# Power.net
KiCad netlist of a schematic drawn in Altium Designer
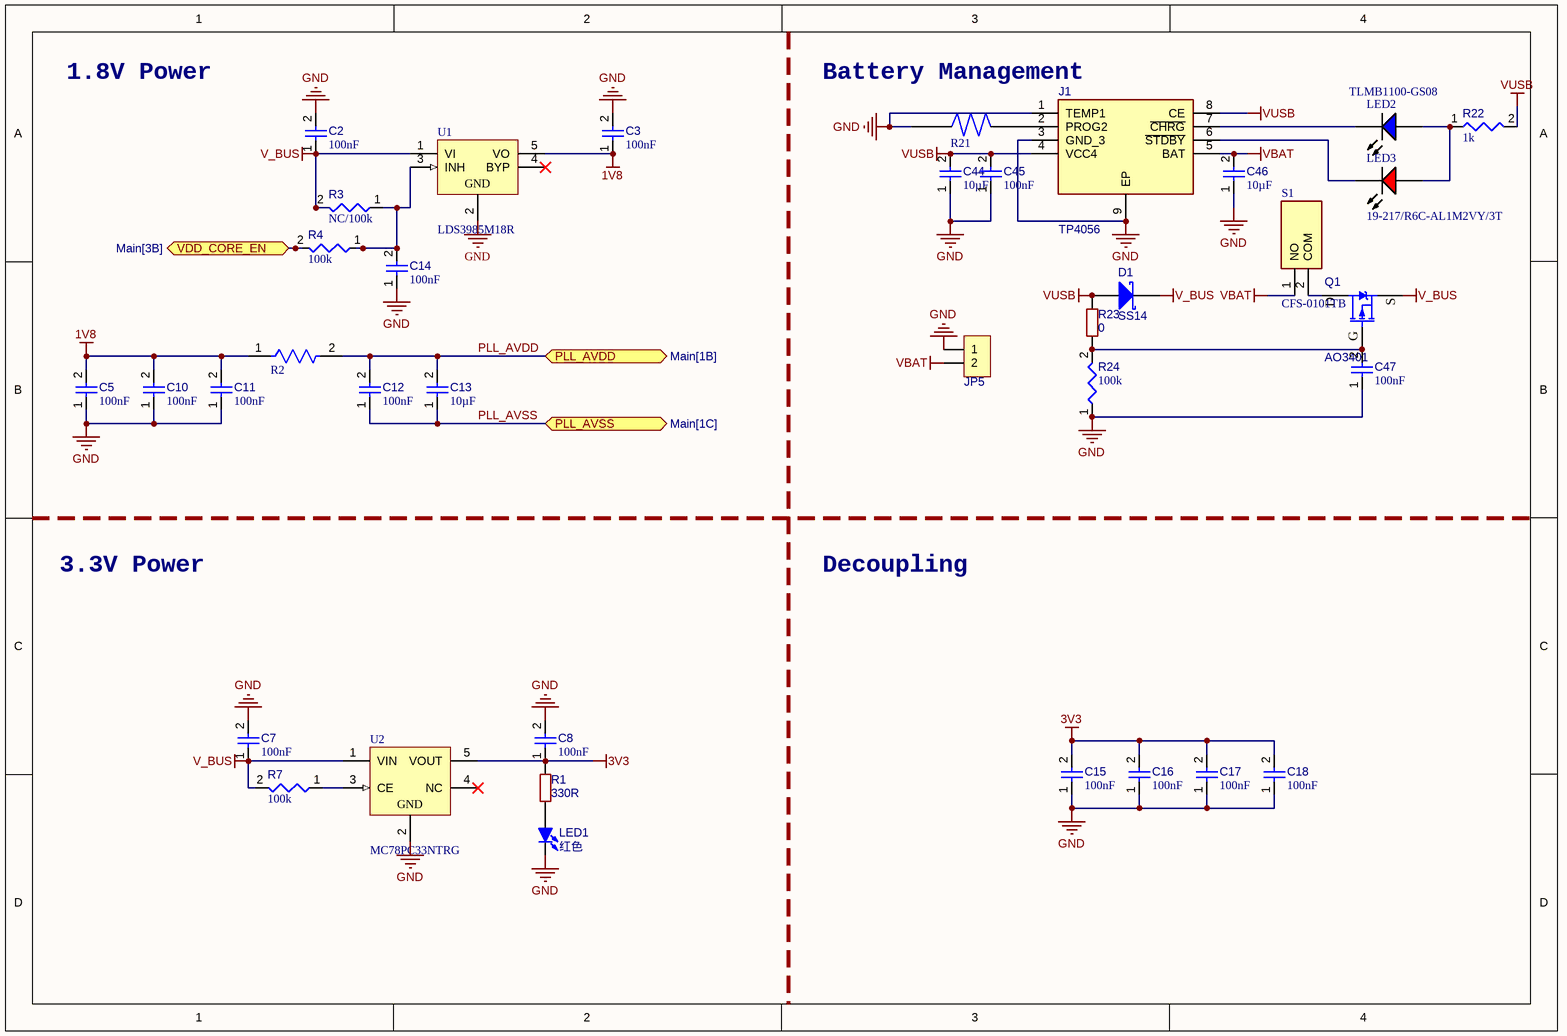
[diagram p0: Power.SchDoc]

(export (version "E")
  (design (tool "Eeschema 10.0.6"))
  (components
    (comp (ref "C2")
      (value "100nF")
      (footprint "CAPC1608X90X40NL10T20")
      (description "Chip Capacitor, 100 nF, +/- 10%, 50 V, 0603 (1608 Metric)")
      (fields (field (name "TOLERANCE") "10%") (field (name "Comment") "Capacitor 100 nF +/-10% 50 V 0603"))
      (libsource (lib "Rice University") (part "CAP-NP-2"))
    )
    (comp (ref "C3")
      (value "100nF")
      (footprint "CAPC1608X90X40NL10T20")
      (description "Chip Capacitor, 100 nF, +/- 10%, 50 V, 0603 (1608 Metric)")
      (fields (field (name "TOLERANCE") "10%") (field (name "Comment") "Capacitor 100 nF +/-10% 50 V 0603"))
      (libsource (lib "Rice University") (part "CAP-NP-2"))
    )
    (comp (ref "C5")
      (value "100nF")
      (footprint "CAPC1608X90X40NL10T20")
      (description "Chip Capacitor, 100 nF, +/- 10%, 50 V, 0603 (1608 Metric)")
      (fields (field (name "TOLERANCE") "10%") (field (name "Comment") "Capacitor 100 nF +/-10% 50 V 0603"))
      (libsource (lib "Rice University") (part "CAP-NP-2"))
    )
    (comp (ref "C7")
      (value "100nF")
      (footprint "CAPC1608X90X40NL10T20")
      (description "Chip Capacitor, 100 nF, +/- 10%, 50 V, 0603 (1608 Metric)")
      (fields (field (name "TOLERANCE") "10%") (field (name "Comment") "Capacitor 100 nF +/-10% 50 V 0603"))
      (libsource (lib "Rice University") (part "CAP-NP-2"))
    )
    (comp (ref "C8")
      (value "100nF")
      (footprint "CAPC1608X90X40NL10T20")
      (description "Chip Capacitor, 100 nF, +/- 10%, 50 V, 0603 (1608 Metric)")
      (fields (field (name "TOLERANCE") "10%") (field (name "Comment") "Capacitor 100 nF +/-10% 50 V 0603"))
      (libsource (lib "Rice University") (part "CAP-NP-2"))
    )
    (comp (ref "C10")
      (value "100nF")
      (footprint "CAPC1608X90X40NL10T20")
      (description "Chip Capacitor, 100 nF, +/- 10%, 50 V, 0603 (1608 Metric)")
      (fields (field (name "TOLERANCE") "10%") (field (name "Comment") "Capacitor 100 nF +/-10% 50 V 0603"))
      (libsource (lib "Rice University") (part "CAP-NP-2"))
    )
    (comp (ref "C11")
      (value "100nF")
      (footprint "CAPC1608X90X40NL10T20")
      (description "Chip Capacitor, 100 nF, +/- 10%, 50 V, 0603 (1608 Metric)")
      (fields (field (name "TOLERANCE") "10%") (field (name "Comment") "Capacitor 100 nF +/-10% 50 V 0603"))
      (libsource (lib "Rice University") (part "CAP-NP-2"))
    )
    (comp (ref "C12")
      (value "100nF")
      (footprint "CAPC1608X90X40NL10T20")
      (description "Chip Capacitor, 100 nF, +/- 10%, 50 V, 0603 (1608 Metric)")
      (fields (field (name "TOLERANCE") "10%") (field (name "Comment") "Capacitor 100 nF +/-10% 50 V 0603"))
      (libsource (lib "Rice University") (part "CAP-NP-2"))
    )
    (comp (ref "C13")
      (value "10µF")
      (footprint "CAPC0603(1608)100_L")
      (description "Chip Capacitor, 10µF +/-20%, 10V, 0603, Thickness 1 mm")
      (fields (field (name "TOLERANCE") "10%") (field (name "Comment") "Capacitor 10µF +/-20% 10V 0603"))
      (libsource (lib "Rice University") (part "CAP-NP-2"))
    )
    (comp (ref "C14")
      (value "100nF")
      (footprint "CAPC1608X90X40NL10T20")
      (description "Chip Capacitor, 100 nF, +/- 10%, 50 V, 0603 (1608 Metric)")
      (fields (field (name "TOLERANCE") "10%") (field (name "Comment") "Capacitor 100 nF +/-10% 50 V 0603"))
      (libsource (lib "Rice University") (part "CAP-NP-2"))
    )
    (comp (ref "C15")
      (value "100nF")
      (footprint "CAPC1608X90X40NL10T20")
      (description "Chip Capacitor, 100 nF, +/- 10%, 50 V, 0603 (1608 Metric)")
      (fields (field (name "TOLERANCE") "10%") (field (name "Comment") "Capacitor 100 nF +/-10% 50 V 0603"))
      (libsource (lib "Rice University") (part "CAP-NP-2"))
    )
    (comp (ref "C16")
      (value "100nF")
      (footprint "CAPC1608X90X40NL10T20")
      (description "Chip Capacitor, 100 nF, +/- 10%, 50 V, 0603 (1608 Metric)")
      (fields (field (name "TOLERANCE") "10%") (field (name "Comment") "Capacitor 100 nF +/-10% 50 V 0603"))
      (libsource (lib "Rice University") (part "CAP-NP-2"))
    )
    (comp (ref "C17")
      (value "100nF")
      (footprint "CAPC1608X90X40NL10T20")
      (description "Chip Capacitor, 100 nF, +/- 10%, 50 V, 0603 (1608 Metric)")
      (fields (field (name "TOLERANCE") "10%") (field (name "Comment") "Capacitor 100 nF +/-10% 50 V 0603"))
      (libsource (lib "Rice University") (part "CAP-NP-2"))
    )
    (comp (ref "C18")
      (value "100nF")
      (footprint "CAPC1608X90X40NL10T20")
      (description "Chip Capacitor, 100 nF, +/- 10%, 50 V, 0603 (1608 Metric)")
      (fields (field (name "TOLERANCE") "10%") (field (name "Comment") "Capacitor 100 nF +/-10% 50 V 0603"))
      (libsource (lib "Rice University") (part "CAP-NP-2"))
    )
    (comp (ref "C44")
      (value "10µF")
      (footprint "CAPC0603(1608)100_L")
      (description "Chip Capacitor, 10µF +/-20%, 10V, 0603, Thickness 1 mm")
      (fields (field (name "TOLERANCE") "10%") (field (name "Comment") "Capacitor 10µF +/-20% 10V 0603"))
      (libsource (lib "Rice University") (part "CAP-NP-2"))
    )
    (comp (ref "C45")
      (value "100nF")
      (footprint "CAPC1608X90X40NL10T20")
      (description "Chip Capacitor, 100 nF, +/- 10%, 50 V, 0603 (1608 Metric)")
      (fields (field (name "TOLERANCE") "10%") (field (name "Comment") "Capacitor 100 nF +/-10% 50 V 0603"))
      (libsource (lib "Rice University") (part "CAP-NP-2"))
    )
    (comp (ref "C46")
      (value "10µF")
      (footprint "CAPC0603(1608)100_L")
      (description "Chip Capacitor, 10µF +/-20%, 10V, 0603, Thickness 1 mm")
      (fields (field (name "TOLERANCE") "10%") (field (name "Comment") "Capacitor 10µF +/-20% 10V 0603"))
      (libsource (lib "Rice University") (part "CAP-NP-2"))
    )
    (comp (ref "C47")
      (value "100nF")
      (footprint "CAPC1608X90X40NL10T20")
      (description "Chip Capacitor, 100 nF, +/- 10%, 50 V, 0603 (1608 Metric)")
      (fields (field (name "TOLERANCE") "10%") (field (name "Comment") "Capacitor 100 nF +/-10% 50 V 0603"))
      (libsource (lib "Rice University") (part "CAP-NP-2"))
    )
    (comp (ref "D1")
      (value "SS14")
      (footprint "SMA")
      (description "肖特基二极管")
      (libsource (lib "0.2 - 二极管-TVS-ESD-整流桥-放电管") (part "SS14"))
    )
    (comp (ref "J1")
      (value "TP4056")
      (footprint "SamacSys:SOIC127P600X175-9N")
      (description "Connector")
      (libsource (lib "*") (part "TP4056"))
    )
    (comp (ref "JP5")
      (value "HDR-1X2")
      (footprint "XH2.54-LS-2P")
      (description "2P接插件")
      (libsource (lib "5.5 - 2.54mm连接器(KF2EDGK_XH2.54_2.54排针排母)") (part "Header 2"))
    )
    (comp (ref "LED1")
      (value "红色")
      (footprint "LED0603_R")
      (description "贴片LED")
      (libsource (lib "0.3 - LED发光二极管-IR二极管_接收管-光耦") (part "LED-SMD"))
    )
    (comp (ref "LED2")
      (value "TLMB1100-GS08")
      (footprint "VISH-TLMX1100-2_V")
      (description "Blue LED, 10 mA, 3.9 V, -40 to 100 degC, 2-Pin SMD (0603), RoHS, Tape and Reel")
      (fields (field (name "POWER") "68mW") (field (name "MANUFACTURER") "Vishay Semiconductor"))
      (libsource (lib "Rice University") (part "LED-BLUE-AK-2"))
    )
    (comp (ref "LED3")
      (value "19-217/R6C-AL1M2VY/3T")
      (footprint "EVRL-0603-2_V")
      (description "Chip LED, Red, 5 V, 25 mA, -40 to 85 degC, 2-Pin SMD (0603), RoHS, Tape and Reel")
      (fields (field (name "MANUFACTURER") "Everlight Electronics"))
      (libsource (lib "Rice University") (part "LED-RED-AK-2"))
    )
    (comp (ref "Q1")
      (value "AO3401")
      (footprint "SOT23-3N")
      (description "P沟道 30V/4.2A")
      (libsource (lib "0.4 - 三极管-场效应管-可控硅") (part "AO3401"))
    )
    (comp (ref "R1")
      (value "330R")
      (footprint "R0603_NS")
      (description "贴片电阻")
      (libsource (lib "") (part "R_1"))
    )
    (comp (ref "R2")
      (value "CRGP0603F100R")
      (footprint "FP-CRGP0603-IPC_B")
      (description "Res Thick Film 0603 100 Ohm 1% 0.25W(1/4W) ±100ppm/C Pad SMD T/R")
      (libsource (lib "Rice University") (part "1029c3af85768c4190bb7ad29bc67b5"))
    )
    (comp (ref "R3")
      (value "NC/100k")
      (footprint "RESC1608X55X25ML10T15")
      (description "Chip Resistor, 100 KOhm, +/- 1%, 0.1 W, -55 to 155 degC, 0603 (1608 Metric)")
      (fields (field (name "TOLERANCE") "1%") (field (name "POWER") "100mW"))
      (libsource (lib "Rice University") (part "RES-2"))
    )
    (comp (ref "R4")
      (value "100k")
      (footprint "RESC1608X55X25ML10T15")
      (description "Chip Resistor, 100 KOhm, +/- 1%, 0.1 W, -55 to 155 degC, 0603 (1608 Metric)")
      (fields (field (name "TOLERANCE") "1%") (field (name "POWER") "100mW"))
      (libsource (lib "Rice University") (part "RES-2"))
    )
    (comp (ref "R7")
      (value "100k")
      (footprint "RESC1608X55X25ML10T15")
      (description "Chip Resistor, 100 KOhm, +/- 1%, 0.1 W, -55 to 155 degC, 0603 (1608 Metric)")
      (fields (field (name "TOLERANCE") "1%") (field (name "POWER") "100mW"))
      (libsource (lib "Rice University") (part "RES-2"))
    )
    (comp (ref "R21")
      (value "CRCW06031K20FKTA")
      (footprint "CRCW06031K20FKTA-Footprint-1")
      (description "Res Thick Film 0603 1.2K Ohm 1% 1/10W ±100ppm/°C Molded SMD SMD Paper T/R")
      (libsource (lib "Rice University") (part "CRCW06031K20FKTA-Symbol-1"))
    )
    (comp (ref "R22")
      (value "1k")
      (footprint "RESC1608X55X25ML10T15")
      (description "Chip Resistor, 1 KOhm, +/-1%, 0.1 W, -55 to 155 degC, 0603 (1608 Metric)")
      (fields (field (name "POWER") "100mW") (field (name "TOLERANCE") "1%"))
      (libsource (lib "Rice University") (part "RES-2"))
    )
    (comp (ref "R23")
      (value "0")
      (footprint "R0603_NS")
      (description "贴片电阻")
      (libsource (lib "0.1 - 电阻-电容-电感-晶振-晶体-磁珠-电位器-法拉电容-馈通电容") (part "R"))
    )
    (comp (ref "R24")
      (value "100k")
      (footprint "RESC1608X55X25ML10T15")
      (description "Chip Resistor, 100 KOhm, +/- 1%, 0.1 W, -55 to 155 degC, 0603 (1608 Metric)")
      (fields (field (name "TOLERANCE") "1%") (field (name "POWER") "100mW"))
      (libsource (lib "Rice University") (part "RES-2"))
    )
    (comp (ref "S1")
      (value "CFS-0101TB")
      (footprint "SamacSys:CFS0101TB")
      (description "Switch")
      (fields (field (name "MOUSER PART NUMBER") "229-CFS-0101TB"))
      (libsource (lib "*") (part "CFS-0101TB"))
    )
    (comp (ref "U1")
      (value "LDS3985M18R")
      (footprint "SOT23-5L_N")
      (description "LDS3985 Series 1.8 V 300 mA Fixed Surface Mount Voltage Regulator - SOT-23-5")
      (libsource (lib "Rice University") (part "PM-REG-LD3985-SOT5"))
    )
    (comp (ref "U2")
      (value "MC78PC33NTRG")
      (footprint "ONSC-SOT-23-5-1212-01_O_V")
      (fields (field (name "MANUFACTURER") "ON Semiconductor") (field (name "POWER") "250mW"))
      (libsource (lib "Rice University") (part "ONSC-MC78PC-SOT-23-5"))
    )
  )
  (nets
    (net (code "1") (name "/PLL_AVDD") (class "Default")
      (node (ref "C12") (pin "2") (pinfunction "2_2") (pintype "passive"))
      (node (ref "C13") (pin "2") (pinfunction "2_2") (pintype "passive"))
      (node (ref "R2") (pin "2") (pinfunction "2_2") (pintype "passive"))
    )
    (net (code "2") (name "/PLL_AVSS") (class "Default")
      (node (ref "C12") (pin "1") (pinfunction "1_1") (pintype "passive"))
      (node (ref "C13") (pin "1") (pinfunction "1_1") (pintype "passive"))
    )
    (net (code "3") (name "/VDD_CORE_EN") (class "Default")
      (node (ref "R4") (pin "2") (pinfunction "2_2") (pintype "passive"))
    )
    (net (code "4") (name "1V8") (class "Default")
      (node (ref "C10") (pin "2") (pinfunction "2_2") (pintype "passive"))
      (node (ref "C11") (pin "2") (pinfunction "2_2") (pintype "passive"))
      (node (ref "C3") (pin "1") (pinfunction "1_1") (pintype "passive"))
      (node (ref "C5") (pin "2") (pinfunction "2_2") (pintype "passive"))
      (node (ref "R2") (pin "1") (pinfunction "1_1") (pintype "passive"))
      (node (ref "U1") (pin "5") (pinfunction "VO_5") (pintype "power_in"))
    )
    (net (code "5") (name "3V3") (class "Default")
      (node (ref "C15") (pin "2") (pinfunction "2_2") (pintype "passive"))
      (node (ref "C16") (pin "2") (pinfunction "2_2") (pintype "passive"))
      (node (ref "C17") (pin "2") (pinfunction "2_2") (pintype "passive"))
      (node (ref "C18") (pin "2") (pinfunction "2_2") (pintype "passive"))
      (node (ref "C8") (pin "1") (pinfunction "1_1") (pintype "passive"))
      (node (ref "R1") (pin "1") (pinfunction "1_1") (pintype "passive"))
      (node (ref "U2") (pin "5") (pinfunction "VOUT_5") (pintype "power_in"))
    )
    (net (code "6") (name "GND") (class "Default")
      (node (ref "C10") (pin "1") (pinfunction "1_1") (pintype "passive"))
      (node (ref "C11") (pin "1") (pinfunction "1_1") (pintype "passive"))
      (node (ref "C14") (pin "1") (pinfunction "1_1") (pintype "passive"))
      (node (ref "C15") (pin "1") (pinfunction "1_1") (pintype "passive"))
      (node (ref "C16") (pin "1") (pinfunction "1_1") (pintype "passive"))
      (node (ref "C17") (pin "1") (pinfunction "1_1") (pintype "passive"))
      (node (ref "C18") (pin "1") (pinfunction "1_1") (pintype "passive"))
      (node (ref "C2") (pin "2") (pinfunction "2_2") (pintype "passive"))
      (node (ref "C3") (pin "2") (pinfunction "2_2") (pintype "passive"))
      (node (ref "C44") (pin "1") (pinfunction "1_1") (pintype "passive"))
      (node (ref "C45") (pin "1") (pinfunction "1_1") (pintype "passive"))
      (node (ref "C46") (pin "1") (pinfunction "1_1") (pintype "passive"))
      (node (ref "C47") (pin "1") (pinfunction "1_1") (pintype "passive"))
      (node (ref "C5") (pin "1") (pinfunction "1_1") (pintype "passive"))
      (node (ref "C7") (pin "2") (pinfunction "2_2") (pintype "passive"))
      (node (ref "C8") (pin "2") (pinfunction "2_2") (pintype "passive"))
      (node (ref "J1") (pin "1") (pinfunction "TEMP1_1") (pintype "passive"))
      (node (ref "J1") (pin "3") (pinfunction "GND_3_3") (pintype "passive"))
      (node (ref "J1") (pin "9") (pinfunction "EP_9") (pintype "passive"))
      (node (ref "JP5") (pin "1") (pinfunction "1_1") (pintype "passive"))
      (node (ref "LED1") (pin "2") (pinfunction "K_2") (pintype "passive"))
      (node (ref "R21") (pin "1") (pinfunction "1_1") (pintype "passive"))
      (node (ref "R24") (pin "1") (pinfunction "1_1") (pintype "passive"))
      (node (ref "U1") (pin "2") (pinfunction "GND_2") (pintype "power_in"))
      (node (ref "U2") (pin "2") (pinfunction "GND_2") (pintype "power_in"))
    )
    (net (code "7") (name "Net-(J1-PROG2)") (class "Default")
      (node (ref "J1") (pin "2") (pinfunction "PROG2_2") (pintype "passive"))
      (node (ref "R21") (pin "2") (pinfunction "2_2") (pintype "passive"))
    )
    (net (code "8") (name "Net-(J1-~{CHRG})") (class "Default")
      (node (ref "J1") (pin "7") (pinfunction "~{CHRG}_7") (pintype "passive"))
      (node (ref "LED2") (pin "2") (pinfunction "K_2") (pintype "passive"))
    )
    (net (code "9") (name "Net-(J1-~{STDBY})") (class "Default")
      (node (ref "J1") (pin "6") (pinfunction "~{STDBY}_6") (pintype "passive"))
      (node (ref "LED3") (pin "2") (pinfunction "K_2") (pintype "passive"))
    )
    (net (code "10") (name "Net-(LED1-A)") (class "Default")
      (node (ref "LED1") (pin "1") (pinfunction "A_1") (pintype "passive"))
      (node (ref "R1") (pin "2") (pinfunction "2_2") (pintype "passive"))
    )
    (net (code "11") (name "Net-(LED2-A)") (class "Default")
      (node (ref "LED2") (pin "1") (pinfunction "A_1") (pintype "passive"))
      (node (ref "LED3") (pin "1") (pinfunction "A_1") (pintype "passive"))
      (node (ref "R22") (pin "1") (pinfunction "1_1") (pintype "passive"))
    )
    (net (code "12") (name "Net-(Q1-D)") (class "Default")
      (node (ref "Q1") (pin "3") (pinfunction "D_3") (pintype "passive"))
      (node (ref "S1") (pin "2") (pinfunction "COM_2") (pintype "passive"))
    )
    (net (code "13") (name "Net-(Q1-G)") (class "Default")
      (node (ref "C47") (pin "2") (pinfunction "2_2") (pintype "passive"))
      (node (ref "Q1") (pin "1") (pinfunction "G_1") (pintype "passive"))
      (node (ref "R23") (pin "1") (pinfunction "1_1") (pintype "passive"))
      (node (ref "R24") (pin "2") (pinfunction "2_2") (pintype "passive"))
    )
    (net (code "14") (name "Net-(U1-INH)") (class "Default")
      (node (ref "C14") (pin "2") (pinfunction "2_2") (pintype "passive"))
      (node (ref "R3") (pin "1") (pinfunction "1_1") (pintype "passive"))
      (node (ref "R4") (pin "1") (pinfunction "1_1") (pintype "passive"))
      (node (ref "U1") (pin "3") (pinfunction "INH_3") (pintype "input"))
    )
    (net (code "15") (name "Net-(U2-CE)") (class "Default")
      (node (ref "R7") (pin "1") (pinfunction "1_1") (pintype "passive"))
      (node (ref "U2") (pin "3") (pinfunction "CE_3") (pintype "input"))
    )
    (net (code "16") (name "VBAT") (class "Default")
      (node (ref "C46") (pin "2") (pinfunction "2_2") (pintype "passive"))
      (node (ref "J1") (pin "5") (pinfunction "BAT_5") (pintype "passive"))
      (node (ref "JP5") (pin "2") (pinfunction "2_2") (pintype "passive"))
      (node (ref "S1") (pin "1") (pinfunction "NO_1") (pintype "passive"))
    )
    (net (code "17") (name "VUSB") (class "Default")
      (node (ref "C44") (pin "2") (pinfunction "2_2") (pintype "passive"))
      (node (ref "C45") (pin "2") (pinfunction "2_2") (pintype "passive"))
      (node (ref "D1") (pin "1") (pinfunction "A_1") (pintype "passive"))
      (node (ref "J1") (pin "4") (pinfunction "VCC4_4") (pintype "passive"))
      (node (ref "J1") (pin "8") (pinfunction "CE_8") (pintype "passive"))
      (node (ref "R22") (pin "2") (pinfunction "2_2") (pintype "passive"))
      (node (ref "R23") (pin "2") (pinfunction "2_2") (pintype "passive"))
    )
    (net (code "18") (name "V_BUS") (class "Default")
      (node (ref "C2") (pin "1") (pinfunction "1_1") (pintype "passive"))
      (node (ref "C7") (pin "1") (pinfunction "1_1") (pintype "passive"))
      (node (ref "D1") (pin "2") (pinfunction "K_2") (pintype "passive"))
      (node (ref "Q1") (pin "2") (pinfunction "S_2") (pintype "passive"))
      (node (ref "R3") (pin "2") (pinfunction "2_2") (pintype "passive"))
      (node (ref "R7") (pin "2") (pinfunction "2_2") (pintype "passive"))
      (node (ref "U1") (pin "1") (pinfunction "VI_1") (pintype "power_in"))
      (node (ref "U2") (pin "1") (pinfunction "VIN_1") (pintype "power_in"))
    )
    (net (code "19") (name "unconnected-(U1-BYP-Pad4)") (class "Default")
      (node (ref "U1") (pin "4") (pinfunction "BYP_4") (pintype "passive+no_connect"))
    )
    (net (code "20") (name "unconnected-(U2-NC-Pad4)") (class "Default")
      (node (ref "U2") (pin "4") (pinfunction "NC_4") (pintype "passive+no_connect"))
    )
  )
)
